# Sch_led.net
KiCad netlist of a schematic drawn in Altium Designer
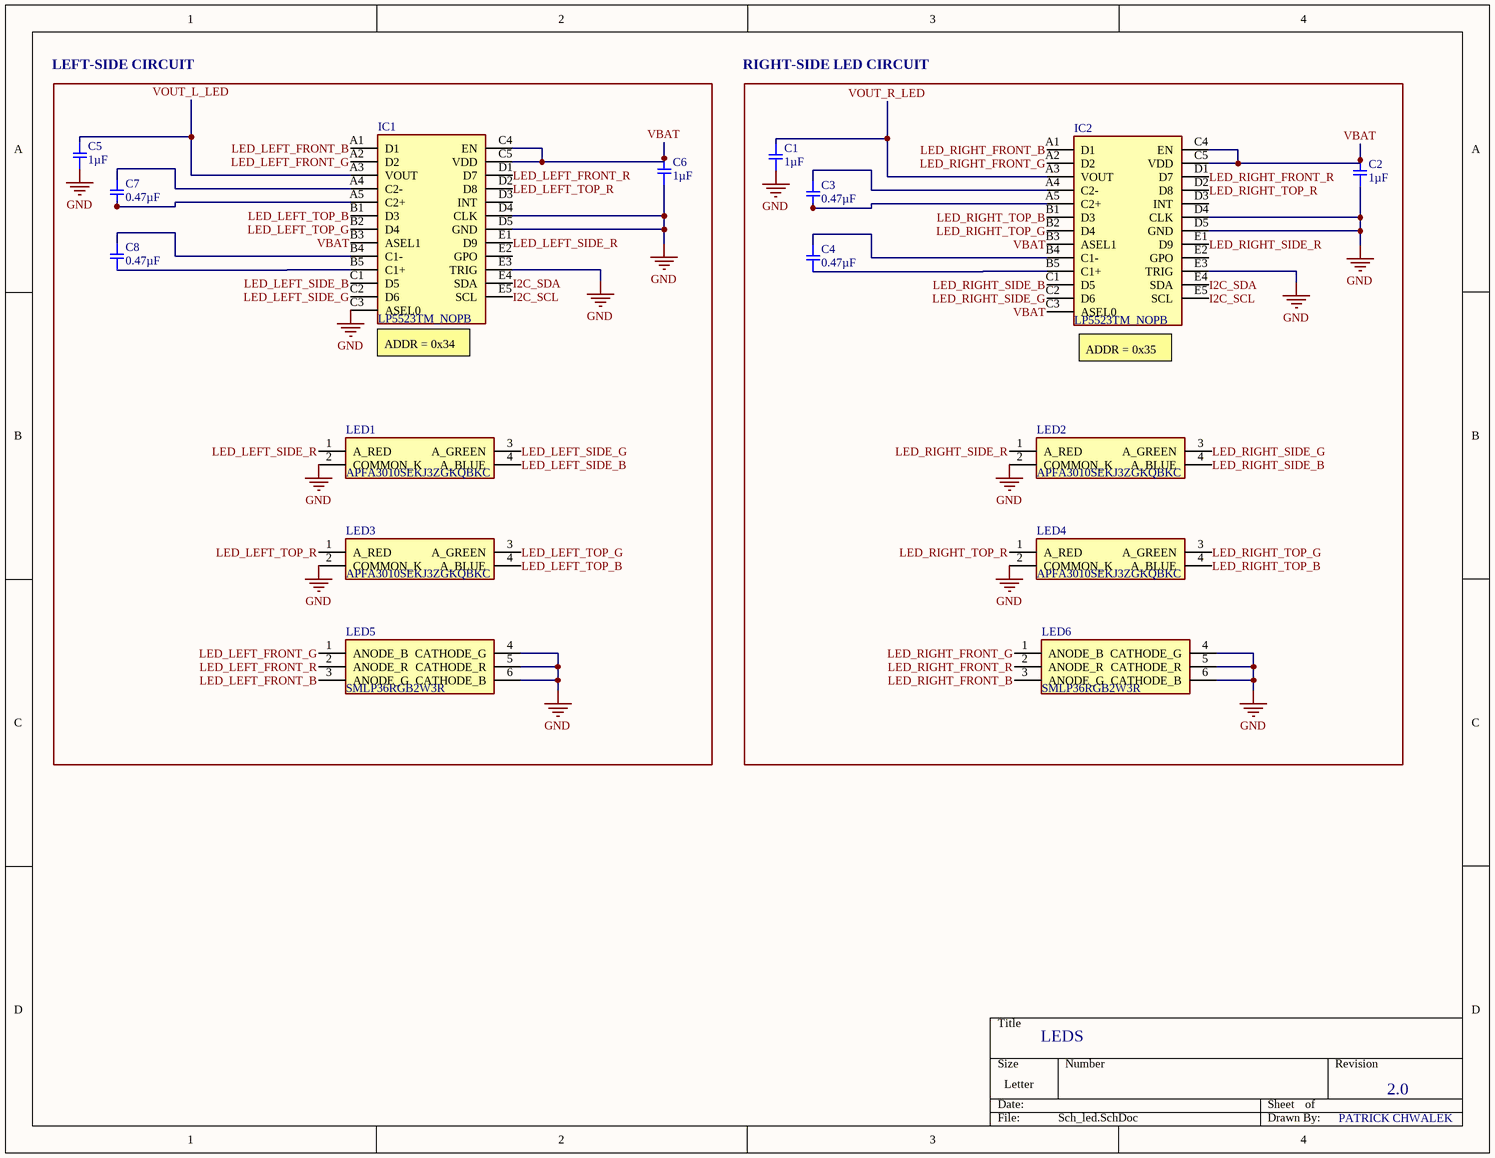
[diagram p0: Sch_led.SchDoc]

(export (version "E")
  (design (tool "Eeschema 10.0.6"))
  (components
    (comp (ref "C1")
      (value "1µF")
      (footprint "0402R")
      (description "CAP CER 1UF 10V X7S 0402")
      (fields
        (field (name "DIGI-KEY PART NUMBER") "490-13409-1-ND")
        (field (name "PART NUMBER") "GCM155C71A105KE38D")
      )
      (libsource (lib "capacitor_murata_0402") (part "GCM155C71A105KE38D"))
    )
    (comp (ref "C2")
      (value "1µF")
      (footprint "0402R")
      (description "CAP CER 1UF 10V X7S 0402")
      (fields
        (field (name "DIGI-KEY PART NUMBER") "490-13409-1-ND")
        (field (name "PART NUMBER") "GCM155C71A105KE38D")
      )
      (libsource (lib "capacitor_murata_0402") (part "GCM155C71A105KE38D"))
    )
    (comp (ref "C3")
      (value "0.47µF")
      (footprint "0402R")
      (description "CAP CER 0.47UF 10V X7S 0402")
      (fields
        (field (name "DIGI-KEY PART NUMBER") "490-13409-1-ND")
        (field (name "PART NUMBER") "GCM155C71A105KE38D")
      )
      (libsource (lib "capacitor_murata_0402") (part "GCM155C71A105KE38D"))
    )
    (comp (ref "C4")
      (value "0.47µF")
      (footprint "0402R")
      (description "CAP CER 0.47UF 10V X7S 0402")
      (fields
        (field (name "DIGI-KEY PART NUMBER") "490-13409-1-ND")
        (field (name "PART NUMBER") "GCM155C71A105KE38D")
      )
      (libsource (lib "capacitor_murata_0402") (part "GCM155C71A105KE38D"))
    )
    (comp (ref "C5")
      (value "1µF")
      (footprint "0402R")
      (description "CAP CER 1UF 10V X7S 0402")
      (fields
        (field (name "DIGI-KEY PART NUMBER") "490-13409-1-ND")
        (field (name "PART NUMBER") "GCM155C71A105KE38D")
      )
      (libsource (lib "capacitor_murata_0402") (part "GCM155C71A105KE38D"))
    )
    (comp (ref "C6")
      (value "1µF")
      (footprint "0402R")
      (description "CAP CER 1UF 10V X7S 0402")
      (fields
        (field (name "DIGI-KEY PART NUMBER") "490-13409-1-ND")
        (field (name "PART NUMBER") "GCM155C71A105KE38D")
      )
      (libsource (lib "capacitor_murata_0402") (part "GCM155C71A105KE38D"))
    )
    (comp (ref "C7")
      (value "0.47µF")
      (footprint "0402R")
      (description "CAP CER 0.47UF 10V X7S 0402")
      (fields
        (field (name "DIGI-KEY PART NUMBER") "490-13409-1-ND")
        (field (name "PART NUMBER") "GCM155C71A105KE38D")
      )
      (libsource (lib "capacitor_murata_0402") (part "GCM155C71A105KE38D"))
    )
    (comp (ref "C8")
      (value "0.47µF")
      (footprint "0402R")
      (description "CAP CER 0.47UF 10V X7S 0402")
      (fields
        (field (name "DIGI-KEY PART NUMBER") "490-13409-1-ND")
        (field (name "PART NUMBER") "GCM155C71A105KE38D")
      )
      (libsource (lib "capacitor_murata_0402") (part "GCM155C71A105KE38D"))
    )
    (comp (ref "IC1")
      (value "LP5523TM_NOPB")
      (footprint "SamacSys:BGA25C40P5X5_226X226X68")
      (description "Integrated Circuit")
      (fields (field (name "MANUFACTURER_PART_NUMBER") "LP5523TM/NOPB"))
      (libsource (lib "*") (part "LP5523TM_NOPB"))
    )
    (comp (ref "IC2")
      (value "LP5523TM_NOPB")
      (footprint "SamacSys:BGA25C40P5X5_226X226X68")
      (description "Integrated Circuit")
      (fields (field (name "MANUFACTURER_PART_NUMBER") "LP5523TM/NOPB"))
      (libsource (lib "*") (part "LP5523TM_NOPB"))
    )
    (comp (ref "LED1")
      (value "APFA3010SEKJ3ZGKQBKC")
      (footprint "SamacSys:KPFA-3010RGBC-11")
      (description "LED")
      (fields (field (name "MOUSER PART NUMBER") "604-APFA3010SEKJ3ZGK"))
      (libsource (lib "*") (part "APFA3010SEKJ3ZGKQBKC"))
    )
    (comp (ref "LED2")
      (value "APFA3010SEKJ3ZGKQBKC")
      (footprint "SamacSys:KPFA-3010RGBC-11")
      (description "LED")
      (fields (field (name "MOUSER PART NUMBER") "604-APFA3010SEKJ3ZGK"))
      (libsource (lib "*") (part "APFA3010SEKJ3ZGKQBKC"))
    )
    (comp (ref "LED3")
      (value "APFA3010SEKJ3ZGKQBKC")
      (footprint "SamacSys:KPFA-3010RGBC-11")
      (description "LED")
      (fields (field (name "MOUSER PART NUMBER") "604-APFA3010SEKJ3ZGK"))
      (libsource (lib "*") (part "APFA3010SEKJ3ZGKQBKC"))
    )
    (comp (ref "LED4")
      (value "APFA3010SEKJ3ZGKQBKC")
      (footprint "SamacSys:KPFA-3010RGBC-11")
      (description "LED")
      (fields (field (name "MOUSER PART NUMBER") "604-APFA3010SEKJ3ZGK"))
      (libsource (lib "*") (part "APFA3010SEKJ3ZGKQBKC"))
    )
    (comp (ref "LED5")
      (value "SMLP36RGB2W3R")
      (footprint "SamacSys:ROHM-1510-(0604)")
      (description "LED")
      (fields
        (field (name "MOUSER PART NUMBER") "755-SMLP36RGB2W3R")
        (field (name "RS PART NUMBER") "1246884")
      )
      (libsource (lib "*") (part "SMLP36RGB2W3R"))
    )
    (comp (ref "LED6")
      (value "SMLP36RGB2W3R")
      (footprint "SamacSys:ROHM-1510-(0604)")
      (description "LED")
      (fields
        (field (name "MOUSER PART NUMBER") "755-SMLP36RGB2W3R")
        (field (name "RS PART NUMBER") "1246884")
      )
      (libsource (lib "*") (part "SMLP36RGB2W3R"))
    )
  )
  (nets
    (net (code "1") (name "/I2C_SCL") (class "Default")
      (node (ref "IC1") (pin "E5") (pinfunction "SCL_E5") (pintype "passive"))
      (node (ref "IC2") (pin "E5") (pinfunction "SCL_E5") (pintype "passive"))
    )
    (net (code "2") (name "/I2C_SDA") (class "Default")
      (node (ref "IC1") (pin "E4") (pinfunction "SDA_E4") (pintype "passive"))
      (node (ref "IC2") (pin "E4") (pinfunction "SDA_E4") (pintype "passive"))
    )
    (net (code "3") (name "/LED_LEFT_FRONT_B") (class "Default")
      (node (ref "IC1") (pin "A1") (pinfunction "D1_A1") (pintype "passive"))
      (node (ref "LED5") (pin "3") (pinfunction "ANODE_G_3") (pintype "passive"))
    )
    (net (code "4") (name "/LED_LEFT_FRONT_G") (class "Default")
      (node (ref "IC1") (pin "A2") (pinfunction "D2_A2") (pintype "passive"))
      (node (ref "LED5") (pin "1") (pinfunction "ANODE_B_1") (pintype "passive"))
    )
    (net (code "5") (name "/LED_LEFT_FRONT_R") (class "Default")
      (node (ref "IC1") (pin "D1") (pinfunction "D7_D1") (pintype "passive"))
      (node (ref "LED5") (pin "2") (pinfunction "ANODE_R_2") (pintype "passive"))
    )
    (net (code "6") (name "/LED_LEFT_SIDE_B") (class "Default")
      (node (ref "IC1") (pin "C1") (pinfunction "D5_C1") (pintype "passive"))
      (node (ref "LED1") (pin "4") (pinfunction "A_BLUE_4") (pintype "passive"))
    )
    (net (code "7") (name "/LED_LEFT_SIDE_G") (class "Default")
      (node (ref "IC1") (pin "C2") (pinfunction "D6_C2") (pintype "passive"))
      (node (ref "LED1") (pin "3") (pinfunction "A_GREEN_3") (pintype "passive"))
    )
    (net (code "8") (name "/LED_LEFT_SIDE_R") (class "Default")
      (node (ref "IC1") (pin "E1") (pinfunction "D9_E1") (pintype "passive"))
      (node (ref "LED1") (pin "1") (pinfunction "A_RED_1") (pintype "passive"))
    )
    (net (code "9") (name "/LED_LEFT_TOP_B") (class "Default")
      (node (ref "IC1") (pin "B1") (pinfunction "D3_B1") (pintype "passive"))
      (node (ref "LED3") (pin "4") (pinfunction "A_BLUE_4") (pintype "passive"))
    )
    (net (code "10") (name "/LED_LEFT_TOP_G") (class "Default")
      (node (ref "IC1") (pin "B2") (pinfunction "D4_B2") (pintype "passive"))
      (node (ref "LED3") (pin "3") (pinfunction "A_GREEN_3") (pintype "passive"))
    )
    (net (code "11") (name "/LED_LEFT_TOP_R") (class "Default")
      (node (ref "IC1") (pin "D2") (pinfunction "D8_D2") (pintype "passive"))
      (node (ref "LED3") (pin "1") (pinfunction "A_RED_1") (pintype "passive"))
    )
    (net (code "12") (name "/LED_RIGHT_FRONT_B") (class "Default")
      (node (ref "IC2") (pin "A1") (pinfunction "D1_A1") (pintype "passive"))
      (node (ref "LED6") (pin "3") (pinfunction "ANODE_G_3") (pintype "passive"))
    )
    (net (code "13") (name "/LED_RIGHT_FRONT_G") (class "Default")
      (node (ref "IC2") (pin "A2") (pinfunction "D2_A2") (pintype "passive"))
      (node (ref "LED6") (pin "1") (pinfunction "ANODE_B_1") (pintype "passive"))
    )
    (net (code "14") (name "/LED_RIGHT_FRONT_R") (class "Default")
      (node (ref "IC2") (pin "D1") (pinfunction "D7_D1") (pintype "passive"))
      (node (ref "LED6") (pin "2") (pinfunction "ANODE_R_2") (pintype "passive"))
    )
    (net (code "15") (name "/LED_RIGHT_SIDE_B") (class "Default")
      (node (ref "IC2") (pin "C1") (pinfunction "D5_C1") (pintype "passive"))
      (node (ref "LED2") (pin "4") (pinfunction "A_BLUE_4") (pintype "passive"))
    )
    (net (code "16") (name "/LED_RIGHT_SIDE_G") (class "Default")
      (node (ref "IC2") (pin "C2") (pinfunction "D6_C2") (pintype "passive"))
      (node (ref "LED2") (pin "3") (pinfunction "A_GREEN_3") (pintype "passive"))
    )
    (net (code "17") (name "/LED_RIGHT_SIDE_R") (class "Default")
      (node (ref "IC2") (pin "E1") (pinfunction "D9_E1") (pintype "passive"))
      (node (ref "LED2") (pin "1") (pinfunction "A_RED_1") (pintype "passive"))
    )
    (net (code "18") (name "/LED_RIGHT_TOP_B") (class "Default")
      (node (ref "IC2") (pin "B1") (pinfunction "D3_B1") (pintype "passive"))
      (node (ref "LED4") (pin "4") (pinfunction "A_BLUE_4") (pintype "passive"))
    )
    (net (code "19") (name "/LED_RIGHT_TOP_G") (class "Default")
      (node (ref "IC2") (pin "B2") (pinfunction "D4_B2") (pintype "passive"))
      (node (ref "LED4") (pin "3") (pinfunction "A_GREEN_3") (pintype "passive"))
    )
    (net (code "20") (name "/LED_RIGHT_TOP_R") (class "Default")
      (node (ref "IC2") (pin "D2") (pinfunction "D8_D2") (pintype "passive"))
      (node (ref "LED4") (pin "1") (pinfunction "A_RED_1") (pintype "passive"))
    )
    (net (code "21") (name "/VBAT") (class "Default")
      (node (ref "C2") (pin "2") (pinfunction "2_2") (pintype "passive"))
      (node (ref "C6") (pin "2") (pinfunction "2_2") (pintype "passive"))
      (node (ref "IC1") (pin "B3") (pinfunction "ASEL1_B3") (pintype "passive"))
      (node (ref "IC1") (pin "C4") (pinfunction "EN_C4") (pintype "passive"))
      (node (ref "IC1") (pin "C5") (pinfunction "VDD_C5") (pintype "passive"))
      (node (ref "IC2") (pin "B3") (pinfunction "ASEL1_B3") (pintype "passive"))
      (node (ref "IC2") (pin "C3") (pinfunction "ASEL0_C3") (pintype "passive"))
      (node (ref "IC2") (pin "C4") (pinfunction "EN_C4") (pintype "passive"))
      (node (ref "IC2") (pin "C5") (pinfunction "VDD_C5") (pintype "passive"))
    )
    (net (code "22") (name "/VOUT_L_LED") (class "Default")
      (node (ref "C5") (pin "2") (pinfunction "2_2") (pintype "passive"))
      (node (ref "IC1") (pin "A3") (pinfunction "VOUT_A3") (pintype "passive"))
    )
    (net (code "23") (name "/VOUT_R_LED") (class "Default")
      (node (ref "C1") (pin "2") (pinfunction "2_2") (pintype "passive"))
      (node (ref "IC2") (pin "A3") (pinfunction "VOUT_A3") (pintype "passive"))
    )
    (net (code "24") (name "GND") (class "Default")
      (node (ref "C1") (pin "1") (pinfunction "1_1") (pintype "passive"))
      (node (ref "C2") (pin "1") (pinfunction "1_1") (pintype "passive"))
      (node (ref "C5") (pin "1") (pinfunction "1_1") (pintype "passive"))
      (node (ref "C6") (pin "1") (pinfunction "1_1") (pintype "passive"))
      (node (ref "IC1") (pin "C3") (pinfunction "ASEL0_C3") (pintype "passive"))
      (node (ref "IC1") (pin "D4") (pinfunction "CLK_D4") (pintype "passive"))
      (node (ref "IC1") (pin "D5") (pinfunction "GND_D5") (pintype "passive"))
      (node (ref "IC1") (pin "E3") (pinfunction "TRIG_E3") (pintype "passive"))
      (node (ref "IC2") (pin "D4") (pinfunction "CLK_D4") (pintype "passive"))
      (node (ref "IC2") (pin "D5") (pinfunction "GND_D5") (pintype "passive"))
      (node (ref "IC2") (pin "E3") (pinfunction "TRIG_E3") (pintype "passive"))
      (node (ref "LED1") (pin "2") (pinfunction "COMMON_K_2") (pintype "passive"))
      (node (ref "LED2") (pin "2") (pinfunction "COMMON_K_2") (pintype "passive"))
      (node (ref "LED3") (pin "2") (pinfunction "COMMON_K_2") (pintype "passive"))
      (node (ref "LED4") (pin "2") (pinfunction "COMMON_K_2") (pintype "passive"))
      (node (ref "LED5") (pin "4") (pinfunction "CATHODE_G_4") (pintype "passive"))
      (node (ref "LED5") (pin "5") (pinfunction "CATHODE_R_5") (pintype "passive"))
      (node (ref "LED5") (pin "6") (pinfunction "CATHODE_B_6") (pintype "passive"))
      (node (ref "LED6") (pin "4") (pinfunction "CATHODE_G_4") (pintype "passive"))
      (node (ref "LED6") (pin "5") (pinfunction "CATHODE_R_5") (pintype "passive"))
      (node (ref "LED6") (pin "6") (pinfunction "CATHODE_B_6") (pintype "passive"))
    )
    (net (code "25") (name "Net-(IC1-C1+)") (class "Default")
      (node (ref "C8") (pin "1") (pinfunction "1_1") (pintype "passive"))
      (node (ref "IC1") (pin "B5") (pinfunction "C1+_B5") (pintype "passive"))
    )
    (net (code "26") (name "Net-(IC1-C1-)") (class "Default")
      (node (ref "C8") (pin "2") (pinfunction "2_2") (pintype "passive"))
      (node (ref "IC1") (pin "B4") (pinfunction "C1-_B4") (pintype "passive"))
    )
    (net (code "27") (name "Net-(IC1-C2+)") (class "Default")
      (node (ref "C7") (pin "1") (pinfunction "1_1") (pintype "passive"))
      (node (ref "IC1") (pin "A5") (pinfunction "C2+_A5") (pintype "passive"))
    )
    (net (code "28") (name "Net-(IC1-C2-)") (class "Default")
      (node (ref "C7") (pin "2") (pinfunction "2_2") (pintype "passive"))
      (node (ref "IC1") (pin "A4") (pinfunction "C2-_A4") (pintype "passive"))
    )
    (net (code "29") (name "Net-(IC2-C1+)") (class "Default")
      (node (ref "C4") (pin "1") (pinfunction "1_1") (pintype "passive"))
      (node (ref "IC2") (pin "B5") (pinfunction "C1+_B5") (pintype "passive"))
    )
    (net (code "30") (name "Net-(IC2-C1-)") (class "Default")
      (node (ref "C4") (pin "2") (pinfunction "2_2") (pintype "passive"))
      (node (ref "IC2") (pin "B4") (pinfunction "C1-_B4") (pintype "passive"))
    )
    (net (code "31") (name "Net-(IC2-C2+)") (class "Default")
      (node (ref "C3") (pin "1") (pinfunction "1_1") (pintype "passive"))
      (node (ref "IC2") (pin "A5") (pinfunction "C2+_A5") (pintype "passive"))
    )
    (net (code "32") (name "Net-(IC2-C2-)") (class "Default")
      (node (ref "C3") (pin "2") (pinfunction "2_2") (pintype "passive"))
      (node (ref "IC2") (pin "A4") (pinfunction "C2-_A4") (pintype "passive"))
    )
    (net (code "33") (name "unconnected-(IC1-GPO-PadE2)") (class "Default")
      (node (ref "IC1") (pin "E2") (pinfunction "GPO_E2") (pintype "passive"))
    )
    (net (code "34") (name "unconnected-(IC1-INT-PadD3)") (class "Default")
      (node (ref "IC1") (pin "D3") (pinfunction "INT_D3") (pintype "passive"))
    )
    (net (code "35") (name "unconnected-(IC2-GPO-PadE2)") (class "Default")
      (node (ref "IC2") (pin "E2") (pinfunction "GPO_E2") (pintype "passive"))
    )
    (net (code "36") (name "unconnected-(IC2-INT-PadD3)") (class "Default")
      (node (ref "IC2") (pin "D3") (pinfunction "INT_D3") (pintype "passive"))
    )
  )
)
